# Total.net
KiCad netlist of a schematic drawn in Altium Designer
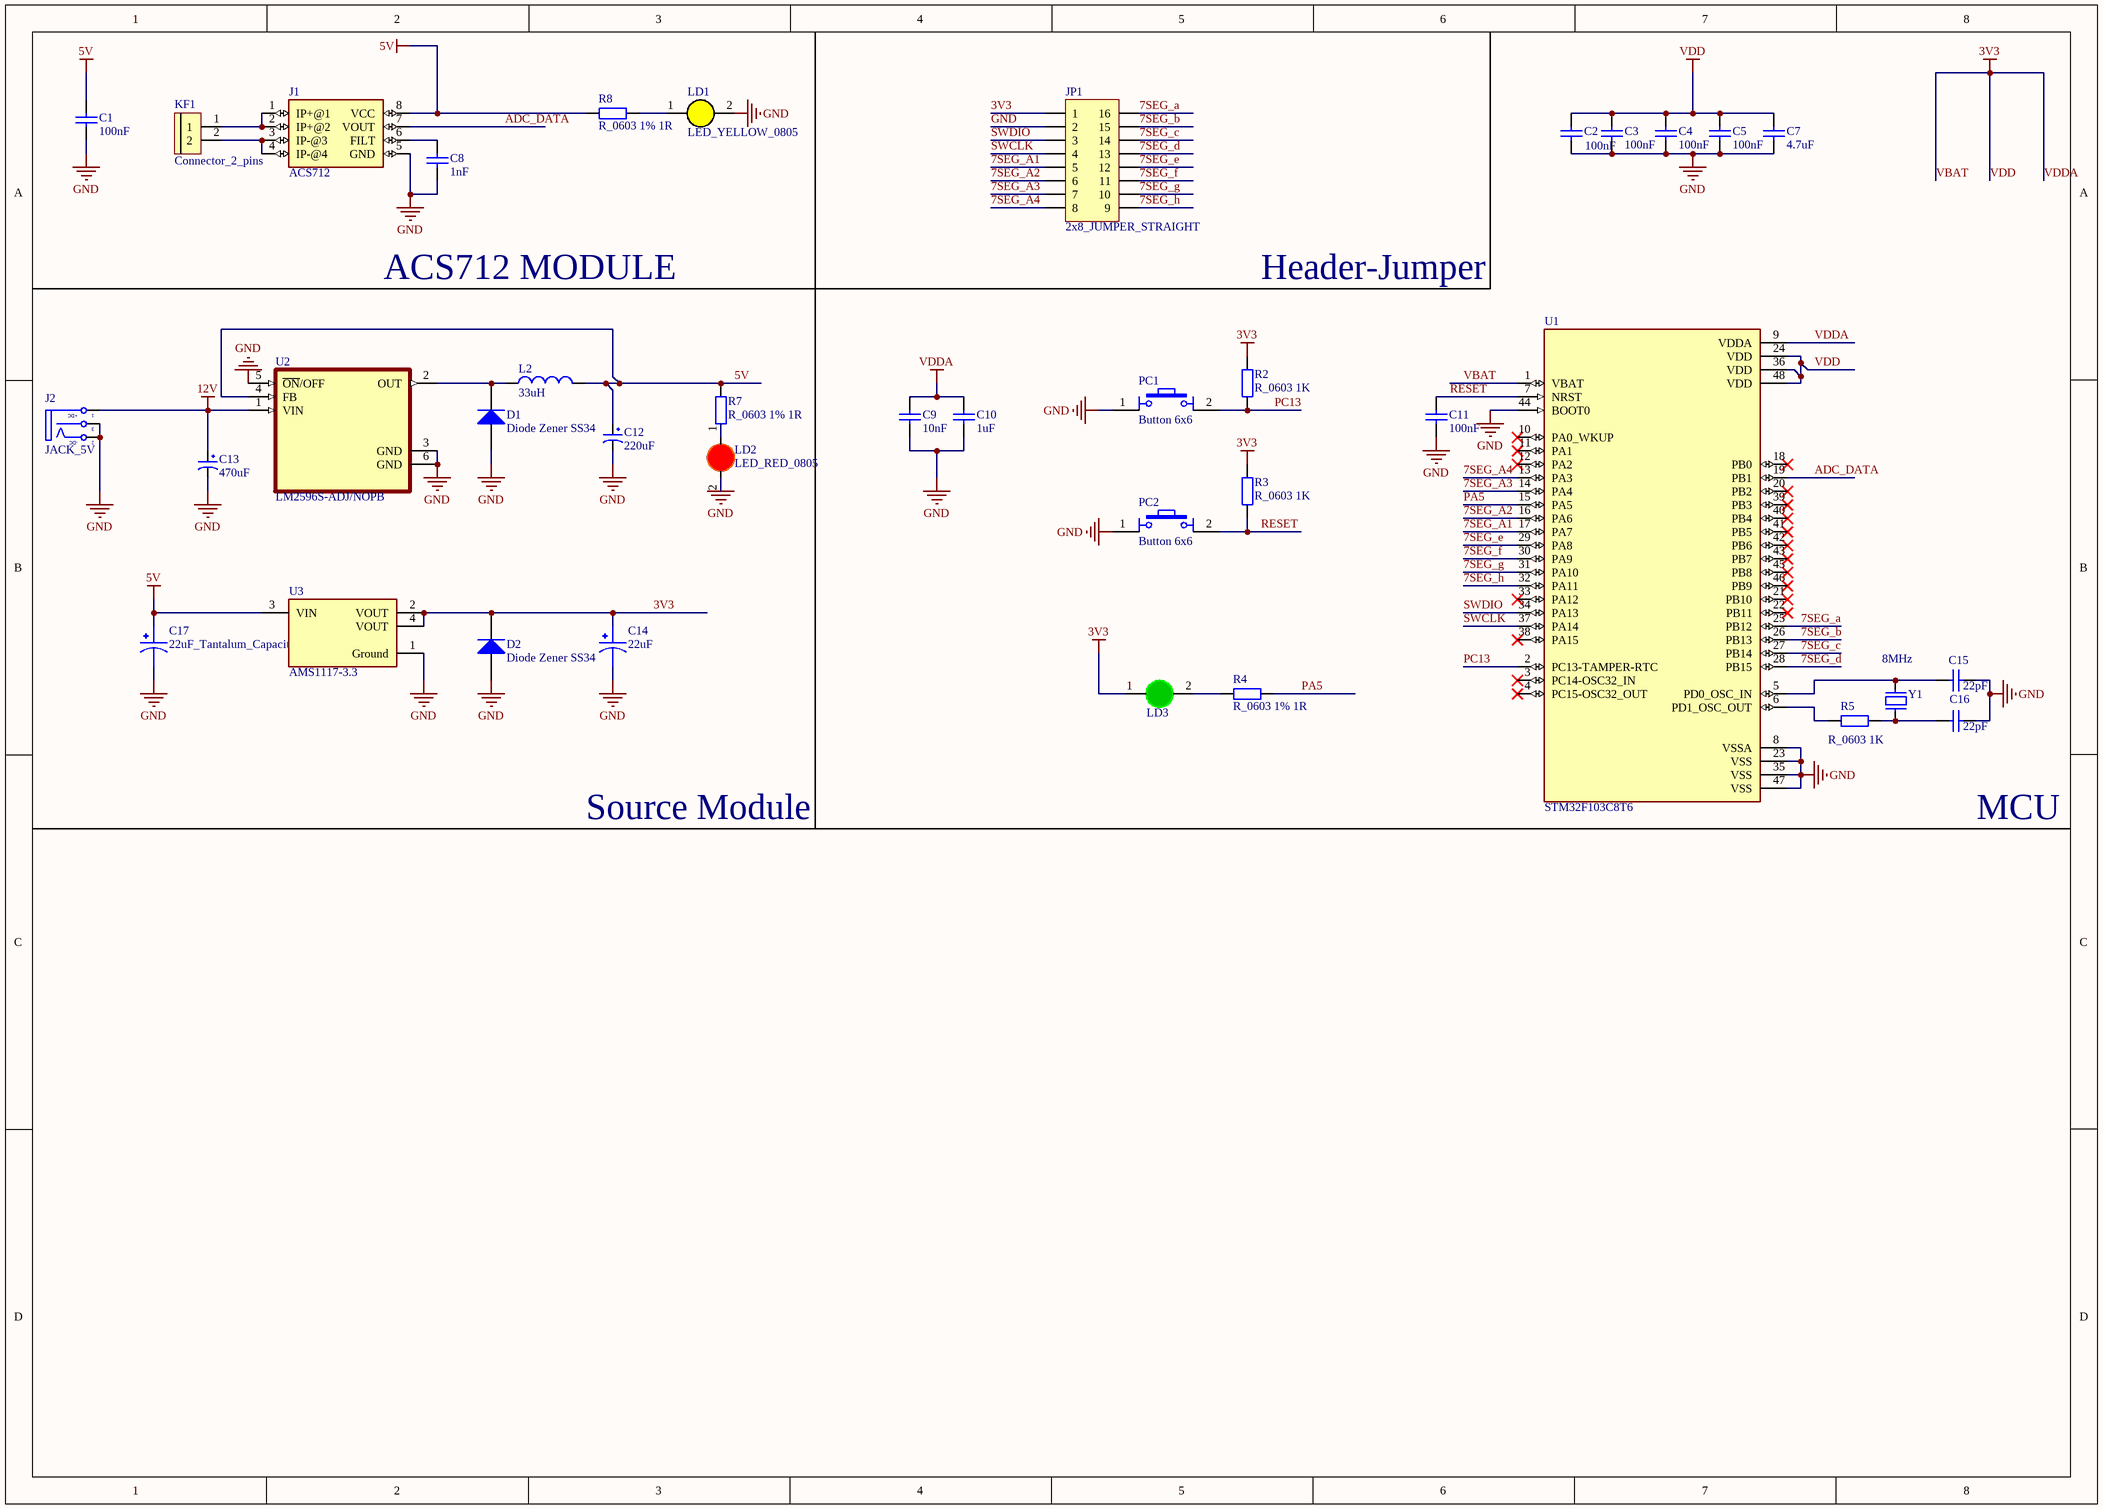
[diagram p0: Total.SchDoc]

(export (version "E")
  (design (tool "Eeschema 10.0.6"))
  (components
    (comp (ref "C1")
      (value "100nF")
      (footprint "CAP 0603")
      (libsource (lib "BKIT_Nguyen_K22") (part "100nF_0603_Ceramic_Capacitor"))
    )
    (comp (ref "C2")
      (value "100nF")
      (footprint "CAP 0603")
      (libsource (lib "BKIT_Nguyen_K22") (part "100nF_0603_Ceramic_Capacitor"))
    )
    (comp (ref "C3")
      (value "100nF")
      (footprint "CAP 0603")
      (libsource (lib "BKIT_Nguyen_K22") (part "100nF_0603_Ceramic_Capacitor"))
    )
    (comp (ref "C4")
      (value "100nF")
      (footprint "CAP 0603")
      (libsource (lib "BKIT_Nguyen_K22") (part "100nF_0603_Ceramic_Capacitor"))
    )
    (comp (ref "C5")
      (value "100nF")
      (footprint "CAP 0603")
      (libsource (lib "BKIT_Nguyen_K22") (part "100nF_0603_Ceramic_Capacitor"))
    )
    (comp (ref "C7")
      (value "4.7uF")
      (footprint "CAP 0603")
      (libsource (lib "BKIT_Nguyen_K22") (part "4.7uF_0603_Ceramic_Capacitor"))
    )
    (comp (ref "C8")
      (value "1nF")
      (footprint "CAP 0603")
      (libsource (lib "BKIT_Nguyen_K22") (part "1nF_0603_Ceramic_Capacitor"))
    )
    (comp (ref "C9")
      (value "10nF")
      (footprint "CAP 0603")
      (libsource (lib "BKIT_Nguyen_K22") (part "10nF_0603_Ceramic_Capacitor"))
    )
    (comp (ref "C10")
      (value "1uF")
      (footprint "CAP 0603")
      (libsource (lib "BKIT_Nguyen_K22") (part "1uF_0603_Ceramic_Capacitor"))
    )
    (comp (ref "C11")
      (value "100nF")
      (footprint "CAP 0603")
      (libsource (lib "BKIT_Nguyen_K22") (part "100nF_0603_Ceramic_Capacitor"))
    )
    (comp (ref "C12")
      (value "220uF")
      (footprint "CAP ALSMD 6.6MM H5.4MM")
      (libsource (lib "BKIT_Nguyen_K22") (part "220uF_10V_Alumium_Capacitor"))
    )
    (comp (ref "C13")
      (value "470uF")
      (footprint "CAP ALSMD ELEC 10.3MM H10.5MM LEADSPANMAX10.9MM")
      (libsource (lib "BKIT_Nguyen_K22") (part "470uF_25V_Alumium_Capacitor"))
    )
    (comp (ref "C14")
      (value "22uF")
      (footprint "CAP POL 6032_280")
      (libsource (lib "BKIT_Nguyen_K22") (part "22uF_Tantalum_Capacitor"))
    )
    (comp (ref "C15")
      (value "22pF")
      (footprint "CAP 0603")
      (libsource (lib "BKIT_Nguyen_K22") (part "22pF_50V_0603_Ceramic_Capacitor"))
    )
    (comp (ref "C16")
      (value "22pF")
      (footprint "CAP 0603")
      (libsource (lib "BKIT_Nguyen_K22") (part "22pF_50V_0603_Ceramic_Capacitor"))
    )
    (comp (ref "C17")
      (value "22uF_Tantalum_Capacitor")
      (footprint "CAP POL 6032_280")
      (libsource (lib "BKIT_Nguyen_K22") (part "22uF_Tantalum_Capacitor"))
    )
    (comp (ref "D1")
      (value "Diode Zener SS34")
      (footprint "CAPMP4226X24N")
      (libsource (lib "BKIT_Nguyen_K22") (part "Diode Zener SS34"))
    )
    (comp (ref "D2")
      (value "Diode Zener SS34")
      (footprint "CAPMP4226X24N")
      (libsource (lib "BKIT_Nguyen_K22") (part "Diode Zener SS34"))
    )
    (comp (ref "J1")
      (value "ACS712")
      (footprint "SO08")
      (description "Current Sensor 20A 1 Channel Hall Effect, Open Loop Bidirectional 8-SOIC (0.154, 3.90mm Width)")
      (fields (field (name "MF") "Allegro MicroSystems"))
      (libsource (lib "BKIT_Nguyen_K22") (part "ACS712"))
    )
    (comp (ref "J2")
      (value "JACK_5V")
      (footprint "JACK DC 5.5")
      (libsource (lib "BKIT_Nguyen_K22") (part "JACK_5V"))
    )
    (comp (ref "JP1")
      (value "2x8_JUMPER_STRAIGHT")
      (footprint "JP 2X8 DT")
      (libsource (lib "BKIT_Nguyen_K22") (part "2x8_JUMPER_STRAIGHT"))
    )
    (comp (ref "KF1")
      (value "Connector_2_pins")
      (footprint "CON2_P196_1729128_TH_ST")
      (libsource (lib "BKIT_Nguyen_K22") (part "Connector_2_pins"))
    )
    (comp (ref "L2")
      (value "33uH")
      (footprint "CDRH127")
      (libsource (lib "BKIT_Nguyen_K22") (part "4.2A_33uH_CDRH127"))
    )
    (comp (ref "LD1")
      (value "LED_YELLOW_0805")
      (footprint "LED-0805-Yellow")
      (libsource (lib "BKIT_Nguyen_K22") (part "LED_YELLOW_0805"))
    )
    (comp (ref "LD2")
      (value "LED_RED_0805")
      (footprint "LED-0805-Red")
      (libsource (lib "BKIT_Nguyen_K22") (part "LED_RED_0805"))
    )
    (comp (ref "LD3")
      (value "LED_GREEN_0805")
      (footprint "LED-0805-Green")
      (libsource (lib "BKIT_Nguyen_K22") (part "LED_GREEN_0805"))
    )
    (comp (ref "PC1")
      (value "Button 6x6")
      (footprint "Nut nhan 4 chan cam 6x6")
      (libsource (lib "BKIT_Nguyen_K22") (part "Button 6x6"))
    )
    (comp (ref "PC2")
      (value "Button 6x6")
      (footprint "Nut nhan 4 chan cam 6x6")
      (libsource (lib "BKIT_Nguyen_K22") (part "Button 6x6"))
    )
    (comp (ref "R2")
      (value "R_0603 1K")
      (footprint "TRO SMD 0603")
      (libsource (lib "BKIT_Nguyen_K22") (part "R_0603 1% 1R"))
    )
    (comp (ref "R3")
      (value "R_0603 1K")
      (footprint "TRO SMD 0603")
      (libsource (lib "BKIT_Nguyen_K22") (part "R_0603 1% 1R"))
    )
    (comp (ref "R4")
      (value "R_0603 1% 1R")
      (footprint "TRO SMD 0603")
      (libsource (lib "BKIT_Nguyen_K22") (part "R_0603 1% 1R"))
    )
    (comp (ref "R5")
      (value "R_0603 1K")
      (footprint "TRO SMD 0603")
      (libsource (lib "BKIT_Nguyen_K22") (part "R_0603 1% 1R"))
    )
    (comp (ref "R7")
      (value "R_0603 1% 1R")
      (footprint "TRO SMD 0603")
      (libsource (lib "BKIT_Nguyen_K22") (part "R_0603 1% 1R"))
    )
    (comp (ref "R8")
      (value "R_0603 1% 1R")
      (footprint "TRO SMD 0603")
      (libsource (lib "BKIT_Nguyen_K22") (part "R_0603 1% 1R"))
    )
    (comp (ref "U1")
      (value "STM32F103C8T6")
      (footprint "QFP50P900X900X160-48N")
      (description "ARM® Cortex®-M3 STM32F1 Microcontroller IC 32-Bit 72MHz 64KB (64K x 8) FLASH 48-LQFP (7x7)")
      (fields (field (name "MF") "STMicroelectronics"))
      (libsource (lib "BKIT_Nguyen_K22") (part "STM32F103C8T6"))
    )
    (comp (ref "U2")
      (value "LM2596S-ADJ/NOPB")
      (footprint "VREG_LM2596S-ADJ/NOPB")
      (description "SIMPLE SWITCHERÂ® 4.5V to 40V, 3A Low Component Count Step-Down Regulator")
      (fields (field (name "MF") "Texas Instruments"))
      (libsource (lib "BKIT_Nguyen_K22") (part "LM2596S-ADJ/NOPB"))
    )
    (comp (ref "U3")
      (value "AMS1117-3.3")
      (footprint "FP-AMS1117-IPC_A")
      (description "LDO Voltage Regulators 1A, 3.3V")
      (fields
        (field (name "OCTOPART") "https://octopart.com/ams1117-3.3-advanced+monolithic+systems-25899300")
        (field (name "MANUFACTURER") "Advanced Monolithic Systems")
      )
      (libsource (lib "BKIT_Nguyen_K22") (part "CMP-209535-000001-1"))
    )
    (comp (ref "Y1")
      (value "8MHz")
      (footprint "Thach Anh 2 Chan SMD")
      (libsource (lib "BKIT_Nguyen_K22") (part "8MHz_Crystal_2p_SMD"))
    )
  )
  (nets
    (net (code "1") (name "/7SEG_A1") (class "Default")
      (node (ref "JP1") (pin "5") (pinfunction "5_5") (pintype "passive"))
      (node (ref "U1") (pin "17") (pinfunction "PA7_17") (pintype "bidirectional"))
    )
    (net (code "2") (name "/7SEG_A2") (class "Default")
      (node (ref "JP1") (pin "6") (pinfunction "6_6") (pintype "passive"))
      (node (ref "U1") (pin "16") (pinfunction "PA6_16") (pintype "bidirectional"))
    )
    (net (code "3") (name "/7SEG_A3") (class "Default")
      (node (ref "JP1") (pin "7") (pinfunction "7_7") (pintype "passive"))
      (node (ref "U1") (pin "14") (pinfunction "PA4_14") (pintype "bidirectional"))
    )
    (net (code "4") (name "/7SEG_A4") (class "Default")
      (node (ref "JP1") (pin "8") (pinfunction "8_8") (pintype "passive"))
      (node (ref "U1") (pin "13") (pinfunction "PA3_13") (pintype "bidirectional"))
    )
    (net (code "5") (name "/7SEG_a") (class "Default")
      (node (ref "JP1") (pin "16") (pinfunction "16_16") (pintype "passive"))
      (node (ref "U1") (pin "25") (pinfunction "PB12_25") (pintype "bidirectional"))
    )
    (net (code "6") (name "/7SEG_b") (class "Default")
      (node (ref "JP1") (pin "15") (pinfunction "15_15") (pintype "passive"))
      (node (ref "U1") (pin "26") (pinfunction "PB13_26") (pintype "bidirectional"))
    )
    (net (code "7") (name "/7SEG_c") (class "Default")
      (node (ref "JP1") (pin "14") (pinfunction "14_14") (pintype "passive"))
      (node (ref "U1") (pin "27") (pinfunction "PB14_27") (pintype "bidirectional"))
    )
    (net (code "8") (name "/7SEG_d") (class "Default")
      (node (ref "JP1") (pin "13") (pinfunction "13_13") (pintype "passive"))
      (node (ref "U1") (pin "28") (pinfunction "PB15_28") (pintype "bidirectional"))
    )
    (net (code "9") (name "/7SEG_e") (class "Default")
      (node (ref "JP1") (pin "12") (pinfunction "12_12") (pintype "passive"))
      (node (ref "U1") (pin "29") (pinfunction "PA8_29") (pintype "bidirectional"))
    )
    (net (code "10") (name "/7SEG_f") (class "Default")
      (node (ref "JP1") (pin "11") (pinfunction "11_11") (pintype "passive"))
      (node (ref "U1") (pin "30") (pinfunction "PA9_30") (pintype "bidirectional"))
    )
    (net (code "11") (name "/7SEG_g") (class "Default")
      (node (ref "JP1") (pin "10") (pinfunction "10_10") (pintype "passive"))
      (node (ref "U1") (pin "31") (pinfunction "PA10_31") (pintype "bidirectional"))
    )
    (net (code "12") (name "/7SEG_h") (class "Default")
      (node (ref "JP1") (pin "9") (pinfunction "9_9") (pintype "passive"))
      (node (ref "U1") (pin "32") (pinfunction "PA11_32") (pintype "bidirectional"))
    )
    (net (code "13") (name "/ADC_DATA") (class "Default")
      (node (ref "J1") (pin "7") (pinfunction "VOUT_7") (pintype "bidirectional"))
      (node (ref "U1") (pin "19") (pinfunction "PB1_19") (pintype "bidirectional"))
    )
    (net (code "14") (name "/PA5") (class "Default")
      (node (ref "R4") (pin "2") (pinfunction "2_2") (pintype "passive"))
      (node (ref "U1") (pin "15") (pinfunction "PA5_15") (pintype "bidirectional"))
    )
    (net (code "15") (name "/PC13") (class "Default")
      (node (ref "PC1") (pin "2") (pintype "passive"))
      (node (ref "R2") (pin "1") (pinfunction "1_1") (pintype "passive"))
      (node (ref "U1") (pin "2") (pinfunction "PC13-TAMPER-RTC_2") (pintype "bidirectional"))
    )
    (net (code "16") (name "/RESET") (class "Default")
      (node (ref "C11") (pin "2") (pinfunction "2_2") (pintype "passive"))
      (node (ref "PC2") (pin "2") (pintype "passive"))
      (node (ref "R3") (pin "1") (pinfunction "1_1") (pintype "passive"))
      (node (ref "U1") (pin "7") (pinfunction "NRST_7") (pintype "input"))
    )
    (net (code "17") (name "/SWCLK") (class "Default")
      (node (ref "JP1") (pin "4") (pinfunction "4_4") (pintype "passive"))
      (node (ref "U1") (pin "37") (pinfunction "PA14_37") (pintype "bidirectional"))
    )
    (net (code "18") (name "/SWDIO") (class "Default")
      (node (ref "JP1") (pin "3") (pinfunction "3_3") (pintype "passive"))
      (node (ref "U1") (pin "34") (pinfunction "PA13_34") (pintype "bidirectional"))
    )
    (net (code "19") (name "3V3") (class "Default")
      (node (ref "C10") (pin "1") (pinfunction "1_1") (pintype "passive"))
      (node (ref "C14") (pin "1") (pinfunction "1_1") (pintype "passive"))
      (node (ref "C2") (pin "1") (pinfunction "1_1") (pintype "passive"))
      (node (ref "C3") (pin "2") (pinfunction "2_2") (pintype "passive"))
      (node (ref "C4") (pin "2") (pinfunction "2_2") (pintype "passive"))
      (node (ref "C5") (pin "1") (pinfunction "1_1") (pintype "passive"))
      (node (ref "C7") (pin "1") (pinfunction "1_1") (pintype "passive"))
      (node (ref "C9") (pin "1") (pinfunction "1_1") (pintype "passive"))
      (node (ref "D2") (pin "2") (pinfunction "2_2") (pintype "passive"))
      (node (ref "JP1") (pin "1") (pinfunction "1_1") (pintype "passive"))
      (node (ref "LD3") (pin "1") (pinfunction "A_1") (pintype "passive"))
      (node (ref "R2") (pin "2") (pinfunction "2_2") (pintype "passive"))
      (node (ref "R3") (pin "2") (pinfunction "2_2") (pintype "passive"))
      (node (ref "U1") (pin "1") (pinfunction "VBAT_1") (pintype "bidirectional"))
      (node (ref "U1") (pin "24") (pinfunction "VDD_24") (pintype "power_in"))
      (node (ref "U1") (pin "36") (pinfunction "VDD_36") (pintype "power_in"))
      (node (ref "U1") (pin "48") (pinfunction "VDD_48") (pintype "power_in"))
      (node (ref "U1") (pin "9") (pinfunction "VDDA_9") (pintype "power_in"))
      (node (ref "U3") (pin "2") (pinfunction "VOUT_2") (pintype "passive"))
      (node (ref "U3") (pin "4") (pinfunction "VOUT_4") (pintype "passive"))
    )
    (net (code "20") (name "5V") (class "Default")
      (node (ref "C1") (pin "1") (pinfunction "1_1") (pintype "passive"))
      (node (ref "C12") (pin "1") (pinfunction "1_1") (pintype "passive"))
      (node (ref "C17") (pin "1") (pinfunction "1_1") (pintype "passive"))
      (node (ref "J1") (pin "8") (pinfunction "VCC_8") (pintype "bidirectional"))
      (node (ref "L2") (pin "2") (pinfunction "2_2") (pintype "passive"))
      (node (ref "R7") (pin "2") (pinfunction "2_2") (pintype "passive"))
      (node (ref "R8") (pin "1") (pinfunction "1_1") (pintype "passive"))
      (node (ref "U2") (pin "4") (pinfunction "FB_4") (pintype "input"))
      (node (ref "U3") (pin "3") (pinfunction "VIN_3") (pintype "power_in"))
    )
    (net (code "21") (name "12V") (class "Default")
      (node (ref "C13") (pin "1") (pinfunction "1_1") (pintype "passive"))
      (node (ref "J2") (pin "1") (pinfunction "T_1") (pintype "passive"))
      (node (ref "U2") (pin "1") (pinfunction "VIN_1") (pintype "input"))
    )
    (net (code "22") (name "GND") (class "Default")
      (node (ref "C1") (pin "2") (pinfunction "2_2") (pintype "passive"))
      (node (ref "C10") (pin "2") (pinfunction "2_2") (pintype "passive"))
      (node (ref "C11") (pin "1") (pinfunction "1_1") (pintype "passive"))
      (node (ref "C12") (pin "2") (pinfunction "2_2") (pintype "passive"))
      (node (ref "C13") (pin "2") (pinfunction "2_2") (pintype "passive"))
      (node (ref "C14") (pin "2") (pinfunction "2_2") (pintype "passive"))
      (node (ref "C15") (pin "1") (pinfunction "1_1") (pintype "passive"))
      (node (ref "C16") (pin "1") (pinfunction "1_1") (pintype "passive"))
      (node (ref "C17") (pin "2") (pinfunction "2_2") (pintype "passive"))
      (node (ref "C2") (pin "2") (pinfunction "2_2") (pintype "passive"))
      (node (ref "C3") (pin "1") (pinfunction "1_1") (pintype "passive"))
      (node (ref "C4") (pin "1") (pinfunction "1_1") (pintype "passive"))
      (node (ref "C5") (pin "2") (pinfunction "2_2") (pintype "passive"))
      (node (ref "C7") (pin "2") (pinfunction "2_2") (pintype "passive"))
      (node (ref "C8") (pin "2") (pinfunction "2_2") (pintype "passive"))
      (node (ref "C9") (pin "2") (pinfunction "2_2") (pintype "passive"))
      (node (ref "D1") (pin "1") (pinfunction "1_1") (pintype "passive"))
      (node (ref "D2") (pin "1") (pinfunction "1_1") (pintype "passive"))
      (node (ref "J1") (pin "5") (pinfunction "GND_5") (pintype "bidirectional"))
      (node (ref "J2") (pin "2") (pinfunction "TN_2") (pintype "passive"))
      (node (ref "J2") (pin "3") (pinfunction "S_3") (pintype "power_in"))
      (node (ref "JP1") (pin "2") (pinfunction "2_2") (pintype "passive"))
      (node (ref "LD1") (pin "2") (pinfunction "K_2") (pintype "passive"))
      (node (ref "LD2") (pin "2") (pinfunction "K_2") (pintype "passive"))
      (node (ref "PC1") (pin "1") (pintype "passive"))
      (node (ref "PC2") (pin "1") (pintype "passive"))
      (node (ref "U1") (pin "23") (pinfunction "VSS_23") (pintype "power_in"))
      (node (ref "U1") (pin "35") (pinfunction "VSS_35") (pintype "power_in"))
      (node (ref "U1") (pin "44") (pinfunction "BOOT0_44") (pintype "input"))
      (node (ref "U1") (pin "47") (pinfunction "VSS_47") (pintype "power_in"))
      (node (ref "U1") (pin "8") (pinfunction "VSSA_8") (pintype "power_in"))
      (node (ref "U2") (pin "3") (pinfunction "GND_3") (pintype "power_in"))
      (node (ref "U2") (pin "5") (pinfunction "~{ON}/OFF_5") (pintype "input"))
      (node (ref "U2") (pin "6") (pinfunction "GND_6") (pintype "power_in"))
      (node (ref "U3") (pin "1") (pinfunction "Ground_1") (pintype "power_in"))
    )
    (net (code "23") (name "Net-(C16-Pad2)") (class "Default")
      (node (ref "C16") (pin "2") (pinfunction "2_2") (pintype "passive"))
      (node (ref "R5") (pin "2") (pinfunction "2_2") (pintype "passive"))
      (node (ref "Y1") (pin "1") (pinfunction "1_1") (pintype "passive"))
    )
    (net (code "24") (name "Net-(J1-FILT)") (class "Default")
      (node (ref "C8") (pin "1") (pinfunction "1_1") (pintype "passive"))
      (node (ref "J1") (pin "6") (pinfunction "FILT_6") (pintype "bidirectional"))
    )
    (net (code "25") (name "Net-(J1-IP+@1)") (class "Default")
      (node (ref "J1") (pin "1") (pinfunction "IP+@1_1") (pintype "bidirectional"))
      (node (ref "J1") (pin "2") (pinfunction "IP+@2_2") (pintype "bidirectional"))
      (node (ref "KF1") (pin "1") (pinfunction "1_1") (pintype "passive"))
    )
    (net (code "26") (name "Net-(J1-IP-@3)") (class "Default")
      (node (ref "J1") (pin "3") (pinfunction "IP-@3_3") (pintype "bidirectional"))
      (node (ref "J1") (pin "4") (pinfunction "IP-@4_4") (pintype "bidirectional"))
      (node (ref "KF1") (pin "2") (pinfunction "2_2") (pintype "passive"))
    )
    (net (code "27") (name "Net-(LD1-A)") (class "Default")
      (node (ref "LD1") (pin "1") (pinfunction "A_1") (pintype "passive"))
      (node (ref "R8") (pin "2") (pinfunction "2_2") (pintype "passive"))
    )
    (net (code "28") (name "Net-(LD2-A)") (class "Default")
      (node (ref "LD2") (pin "1") (pinfunction "A_1") (pintype "passive"))
      (node (ref "R7") (pin "1") (pinfunction "1_1") (pintype "passive"))
    )
    (net (code "29") (name "Net-(LD3-K)") (class "Default")
      (node (ref "LD3") (pin "2") (pinfunction "K_2") (pintype "passive"))
      (node (ref "R4") (pin "1") (pinfunction "1_1") (pintype "passive"))
    )
    (net (code "30") (name "Net-(U1-PD0_OSC_IN)") (class "Default")
      (node (ref "C15") (pin "2") (pinfunction "2_2") (pintype "passive"))
      (node (ref "U1") (pin "5") (pinfunction "PD0_OSC_IN_5") (pintype "bidirectional"))
      (node (ref "Y1") (pin "2") (pinfunction "2_2") (pintype "passive"))
    )
    (net (code "31") (name "Net-(U1-PD1_OSC_OUT)") (class "Default")
      (node (ref "R5") (pin "1") (pinfunction "1_1") (pintype "passive"))
      (node (ref "U1") (pin "6") (pinfunction "PD1_OSC_OUT_6") (pintype "bidirectional"))
    )
    (net (code "32") (name "Net-(U2-OUT)") (class "Default")
      (node (ref "D1") (pin "2") (pinfunction "2_2") (pintype "passive"))
      (node (ref "L2") (pin "1") (pinfunction "1_1") (pintype "passive"))
      (node (ref "U2") (pin "2") (pinfunction "OUT_2") (pintype "output"))
    )
    (net (code "33") (name "unconnected-(U1-PA0_WKUP-Pad10)") (class "Default")
      (node (ref "U1") (pin "10") (pinfunction "PA0_WKUP_10") (pintype "bidirectional+no_connect"))
    )
    (net (code "34") (name "unconnected-(U1-PA1-Pad11)") (class "Default")
      (node (ref "U1") (pin "11") (pinfunction "PA1_11") (pintype "bidirectional+no_connect"))
    )
    (net (code "35") (name "unconnected-(U1-PA2-Pad12)") (class "Default")
      (node (ref "U1") (pin "12") (pinfunction "PA2_12") (pintype "bidirectional+no_connect"))
    )
    (net (code "36") (name "unconnected-(U1-PA12-Pad33)") (class "Default")
      (node (ref "U1") (pin "33") (pinfunction "PA12_33") (pintype "bidirectional+no_connect"))
    )
    (net (code "37") (name "unconnected-(U1-PA15-Pad38)") (class "Default")
      (node (ref "U1") (pin "38") (pinfunction "PA15_38") (pintype "bidirectional+no_connect"))
    )
    (net (code "38") (name "unconnected-(U1-PB0-Pad18)") (class "Default")
      (node (ref "U1") (pin "18") (pinfunction "PB0_18") (pintype "bidirectional+no_connect"))
    )
    (net (code "39") (name "unconnected-(U1-PB2-Pad20)") (class "Default")
      (node (ref "U1") (pin "20") (pinfunction "PB2_20") (pintype "bidirectional+no_connect"))
    )
    (net (code "40") (name "unconnected-(U1-PB3-Pad39)") (class "Default")
      (node (ref "U1") (pin "39") (pinfunction "PB3_39") (pintype "bidirectional+no_connect"))
    )
    (net (code "41") (name "unconnected-(U1-PB4-Pad40)") (class "Default")
      (node (ref "U1") (pin "40") (pinfunction "PB4_40") (pintype "bidirectional+no_connect"))
    )
    (net (code "42") (name "unconnected-(U1-PB5-Pad41)") (class "Default")
      (node (ref "U1") (pin "41") (pinfunction "PB5_41") (pintype "bidirectional+no_connect"))
    )
    (net (code "43") (name "unconnected-(U1-PB6-Pad42)") (class "Default")
      (node (ref "U1") (pin "42") (pinfunction "PB6_42") (pintype "bidirectional+no_connect"))
    )
    (net (code "44") (name "unconnected-(U1-PB7-Pad43)") (class "Default")
      (node (ref "U1") (pin "43") (pinfunction "PB7_43") (pintype "bidirectional+no_connect"))
    )
    (net (code "45") (name "unconnected-(U1-PB8-Pad45)") (class "Default")
      (node (ref "U1") (pin "45") (pinfunction "PB8_45") (pintype "bidirectional+no_connect"))
    )
    (net (code "46") (name "unconnected-(U1-PB9-Pad46)") (class "Default")
      (node (ref "U1") (pin "46") (pinfunction "PB9_46") (pintype "bidirectional+no_connect"))
    )
    (net (code "47") (name "unconnected-(U1-PB10-Pad21)") (class "Default")
      (node (ref "U1") (pin "21") (pinfunction "PB10_21") (pintype "bidirectional+no_connect"))
    )
    (net (code "48") (name "unconnected-(U1-PB11-Pad22)") (class "Default")
      (node (ref "U1") (pin "22") (pinfunction "PB11_22") (pintype "bidirectional+no_connect"))
    )
    (net (code "49") (name "unconnected-(U1-PC14-OSC32_IN-Pad3)") (class "Default")
      (node (ref "U1") (pin "3") (pinfunction "PC14-OSC32_IN_3") (pintype "bidirectional+no_connect"))
    )
    (net (code "50") (name "unconnected-(U1-PC15-OSC32_OUT-Pad4)") (class "Default")
      (node (ref "U1") (pin "4") (pinfunction "PC15-OSC32_OUT_4") (pintype "bidirectional+no_connect"))
    )
  )
)
